# Tiny85_and_4-Pin_Header.net
KiCad netlist of a schematic drawn in EAGLE
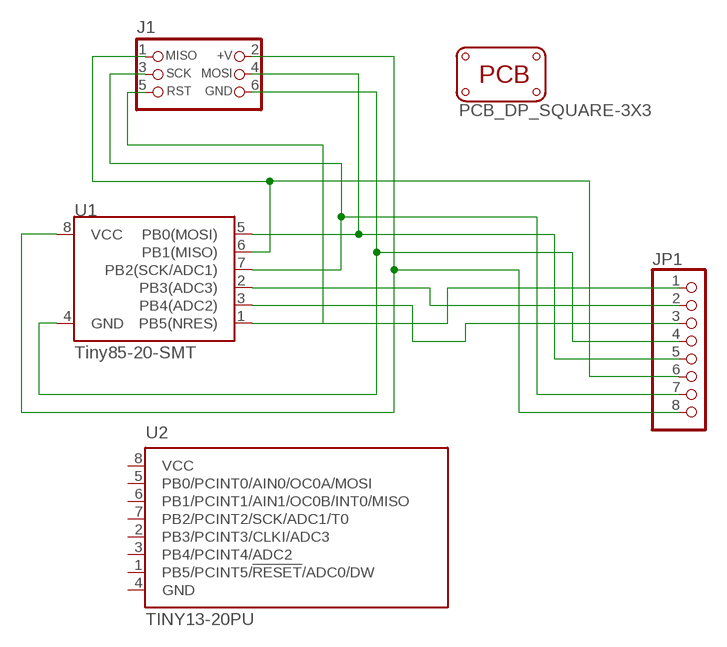
[diagram p0: schematic, sheet 1]

(export (version "E")
  (design (tool "Eeschema 10.0.6"))
  (components
    (comp (ref "J1")
      (value "CON_HEADER_PRG_AVR_ICSP-PTH")
      (footprint "eagle-import:HEADER_PRG_2X03")
      (libsource (lib "eagle-import") (part "CON_HEADER_PRG_AVR_ICSP-PTH"))
    )
    (comp (ref "JP1")
      (value "PINHD-1X8CLEANBIG")
      (footprint "eagle-import:1X08-CLEANBIG")
      (libsource (lib "eagle-import") (part "PINHD-1X8CLEANBIG"))
    )
    (comp (ref "PCB1")
      (value "PCB_DP_SQUARE-3X3")
      (footprint "eagle-import:DP3030_V1")
      (libsource (lib "eagle-import") (part "PCB_DP_SQUARE-3X3"))
    )
    (comp (ref "U1")
      (value "Tiny85-20-SMT")
      (footprint "eagle-import:SO08-EIAJ")
      (libsource (lib "eagle-import") (part "ATTINY45TINY85-20-SMT"))
    )
    (comp (ref "U2")
      (value "TINY13-20PU")
      (footprint "eagle-import:8P3")
      (fields (field (name "MPN") "ATTINY13-20PU"))
      (libsource (lib "eagle-import") (part "TINY13PU-20"))
    )
  )
  (nets
    (net (code "1") (name "/GND") (class "Default")
      (node (ref "U2") (pin "4") (pinfunction "GND_4") (pintype "power_in"))
    )
    (net (code "2") (name "/VCC") (class "Default")
      (node (ref "U2") (pin "8") (pinfunction "VCC_8") (pintype "power_in"))
    )
    (net (code "3") (name "Net-(J1-+V)") (class "Default")
      (node (ref "J1") (pin "2") (pinfunction "+V_2") (pintype "passive"))
      (node (ref "JP1") (pin "8") (pinfunction "8_8") (pintype "passive"))
      (node (ref "U1") (pin "8") (pinfunction "VCC_8") (pintype "bidirectional"))
    )
    (net (code "4") (name "Net-(J1-GND)") (class "Default")
      (node (ref "J1") (pin "6") (pinfunction "GND_6") (pintype "passive"))
      (node (ref "JP1") (pin "4") (pinfunction "4_4") (pintype "passive"))
      (node (ref "U1") (pin "4") (pinfunction "GND_4") (pintype "bidirectional"))
    )
    (net (code "5") (name "Net-(J1-MISO)") (class "Default")
      (node (ref "J1") (pin "1") (pinfunction "MISO_1") (pintype "passive"))
      (node (ref "JP1") (pin "6") (pinfunction "6_6") (pintype "passive"))
      (node (ref "U1") (pin "6") (pinfunction "PB1(MISO)_6") (pintype "bidirectional"))
    )
    (net (code "6") (name "Net-(J1-MOSI)") (class "Default")
      (node (ref "J1") (pin "4") (pinfunction "MOSI_4") (pintype "passive"))
      (node (ref "JP1") (pin "5") (pinfunction "5_5") (pintype "passive"))
      (node (ref "U1") (pin "5") (pinfunction "PB0(MOSI)_5") (pintype "bidirectional"))
    )
    (net (code "7") (name "Net-(J1-RST)") (class "Default")
      (node (ref "J1") (pin "5") (pinfunction "RST_5") (pintype "passive"))
      (node (ref "JP1") (pin "1") (pinfunction "1_1") (pintype "passive"))
      (node (ref "U1") (pin "1") (pinfunction "PB5(NRES)_1") (pintype "bidirectional"))
    )
    (net (code "8") (name "Net-(J1-SCK)") (class "Default")
      (node (ref "J1") (pin "3") (pinfunction "SCK_3") (pintype "passive"))
      (node (ref "JP1") (pin "7") (pinfunction "7_7") (pintype "passive"))
      (node (ref "U1") (pin "7") (pinfunction "PB2(SCK/ADC1)_7") (pintype "bidirectional"))
    )
    (net (code "9") (name "Net-(U1-PB3(ADC3))") (class "Default")
      (node (ref "JP1") (pin "2") (pinfunction "2_2") (pintype "passive"))
      (node (ref "U1") (pin "2") (pinfunction "PB3(ADC3)_2") (pintype "bidirectional"))
    )
    (net (code "10") (name "Net-(U1-PB4(ADC2))") (class "Default")
      (node (ref "JP1") (pin "3") (pinfunction "3_3") (pintype "passive"))
      (node (ref "U1") (pin "3") (pinfunction "PB4(ADC2)_3") (pintype "bidirectional"))
    )
    (net (code "11") (name "unconnected-(U2-PB0{slash}PCINT0{slash}AIN0{slash}OC0A{slash}MOSI-Pad5)") (class "Default")
      (node (ref "U2") (pin "5") (pinfunction "PB0/PCINT0/AIN0/OC0A/MOSI_5") (pintype "bidirectional"))
    )
    (net (code "12") (name "unconnected-(U2-PB1{slash}PCINT1{slash}AIN1{slash}OC0B{slash}INT0{slash}MISO-Pad6)") (class "Default")
      (node (ref "U2") (pin "6") (pinfunction "PB1/PCINT1/AIN1/OC0B/INT0/MISO_6") (pintype "bidirectional"))
    )
    (net (code "13") (name "unconnected-(U2-PB2{slash}PCINT2{slash}SCK{slash}ADC1{slash}T0-Pad7)") (class "Default")
      (node (ref "U2") (pin "7") (pinfunction "PB2/PCINT2/SCK/ADC1/T0_7") (pintype "bidirectional"))
    )
    (net (code "14") (name "unconnected-(U2-PB3{slash}PCINT3{slash}CLKI{slash}ADC3-Pad2)") (class "Default")
      (node (ref "U2") (pin "2") (pinfunction "PB3/PCINT3/CLKI/ADC3_2") (pintype "bidirectional"))
    )
    (net (code "15") (name "unconnected-(U2-PB4{slash}PCINT4{slash}ADC2-Pad3)") (class "Default")
      (node (ref "U2") (pin "3") (pinfunction "PB4/PCINT4/ADC2_3") (pintype "bidirectional"))
    )
    (net (code "16") (name "unconnected-(U2-PB5{slash}PCINT5{slash}~{RESET}{slash}ADC0{slash}DW-Pad1)") (class "Default")
      (node (ref "U2") (pin "1") (pinfunction "PB5/PCINT5/~{RESET}/ADC0/DW_1") (pintype "bidirectional"))
    )
  )
)
